# 5_Keyboard.net
KiCad netlist of a schematic drawn in Altium Designer
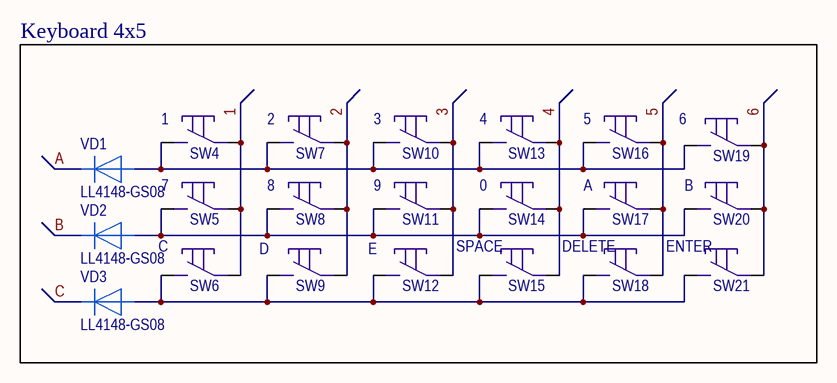
[diagram p0: 5_Keyboard.SchDoc]

(export (version "E")
  (design (tool "Eeschema 10.0.6"))
  (components
    (comp (ref "SW4")
      (value "KLS7-TS6604")
      (footprint "KLS7-TS6604-5.0-180-B")
      (libsource (lib "9.Commutation") (part "KLS7-TS6604"))
    )
    (comp (ref "SW5")
      (value "KLS7-TS6604")
      (footprint "KLS7-TS6604-5.0-180-B")
      (libsource (lib "9.Commutation") (part "KLS7-TS6604"))
    )
    (comp (ref "SW6")
      (value "KLS7-TS6604")
      (footprint "KLS7-TS6604-5.0-180-B")
      (libsource (lib "9.Commutation") (part "KLS7-TS6604"))
    )
    (comp (ref "SW7")
      (value "KLS7-TS6604")
      (footprint "KLS7-TS6604-5.0-180-B")
      (libsource (lib "9.Commutation") (part "KLS7-TS6604"))
    )
    (comp (ref "SW8")
      (value "KLS7-TS6604")
      (footprint "KLS7-TS6604-5.0-180-B")
      (libsource (lib "9.Commutation") (part "KLS7-TS6604"))
    )
    (comp (ref "SW9")
      (value "KLS7-TS6604")
      (footprint "KLS7-TS6604-5.0-180-B")
      (libsource (lib "9.Commutation") (part "KLS7-TS6604"))
    )
    (comp (ref "SW10")
      (value "KLS7-TS6604")
      (footprint "KLS7-TS6604-5.0-180-B")
      (libsource (lib "9.Commutation") (part "KLS7-TS6604"))
    )
    (comp (ref "SW11")
      (value "KLS7-TS6604")
      (footprint "KLS7-TS6604-5.0-180-B")
      (libsource (lib "9.Commutation") (part "KLS7-TS6604"))
    )
    (comp (ref "SW12")
      (value "KLS7-TS6604")
      (footprint "KLS7-TS6604-5.0-180-B")
      (libsource (lib "9.Commutation") (part "KLS7-TS6604"))
    )
    (comp (ref "SW13")
      (value "KLS7-TS6604")
      (footprint "KLS7-TS6604-5.0-180-B")
      (libsource (lib "9.Commutation") (part "KLS7-TS6604"))
    )
    (comp (ref "SW14")
      (value "KLS7-TS6604")
      (footprint "KLS7-TS6604-5.0-180-B")
      (libsource (lib "9.Commutation") (part "KLS7-TS6604"))
    )
    (comp (ref "SW15")
      (value "KLS7-TS6604")
      (footprint "KLS7-TS6604-5.0-180-B")
      (libsource (lib "9.Commutation") (part "KLS7-TS6604"))
    )
    (comp (ref "SW16")
      (value "KLS7-TS6604")
      (footprint "KLS7-TS6604-5.0-180-B")
      (libsource (lib "9.Commutation") (part "KLS7-TS6604"))
    )
    (comp (ref "SW17")
      (value "KLS7-TS6604")
      (footprint "KLS7-TS6604-5.0-180-B")
      (libsource (lib "9.Commutation") (part "KLS7-TS6604"))
    )
    (comp (ref "SW18")
      (value "KLS7-TS6604")
      (footprint "KLS7-TS6604-5.0-180-B")
      (libsource (lib "9.Commutation") (part "KLS7-TS6604"))
    )
    (comp (ref "SW19")
      (value "KLS7-TS6604")
      (footprint "KLS7-TS6604-5.0-180-B")
      (libsource (lib "9.Commutation") (part "KLS7-TS6604"))
    )
    (comp (ref "SW20")
      (value "KLS7-TS6604")
      (footprint "KLS7-TS6604-5.0-180-B")
      (libsource (lib "9.Commutation") (part "KLS7-TS6604"))
    )
    (comp (ref "SW21")
      (value "KLS7-TS6604")
      (footprint "KLS7-TS6604-5.0-180-B")
      (libsource (lib "9.Commutation") (part "KLS7-TS6604"))
    )
    (comp (ref "VD1")
      (value "LL4148-GS08")
      (footprint "SOD-80")
      (description "Диод")
      (libsource (lib "4.Diodes") (part "LL4148-GS08"))
    )
    (comp (ref "VD2")
      (value "LL4148-GS08")
      (footprint "SOD-80")
      (description "Диод")
      (libsource (lib "4.Diodes") (part "LL4148-GS08"))
    )
    (comp (ref "VD3")
      (value "LL4148-GS08")
      (footprint "SOD-80")
      (description "Диод")
      (libsource (lib "4.Diodes") (part "LL4148-GS08"))
    )
  )
  (nets
    (net (code "1") (name "/1") (class "Default")
      (node (ref "SW4") (pin "2") (pinfunction "2_2") (pintype "passive"))
      (node (ref "SW5") (pin "2") (pinfunction "2_2") (pintype "passive"))
      (node (ref "SW6") (pin "2") (pinfunction "2_2") (pintype "passive"))
    )
    (net (code "2") (name "/2") (class "Default")
      (node (ref "SW7") (pin "2") (pinfunction "2_2") (pintype "passive"))
      (node (ref "SW8") (pin "2") (pinfunction "2_2") (pintype "passive"))
      (node (ref "SW9") (pin "2") (pinfunction "2_2") (pintype "passive"))
    )
    (net (code "3") (name "/3") (class "Default")
      (node (ref "SW10") (pin "2") (pinfunction "2_2") (pintype "passive"))
      (node (ref "SW11") (pin "2") (pinfunction "2_2") (pintype "passive"))
      (node (ref "SW12") (pin "2") (pinfunction "2_2") (pintype "passive"))
    )
    (net (code "4") (name "/4") (class "Default")
      (node (ref "SW13") (pin "2") (pinfunction "2_2") (pintype "passive"))
      (node (ref "SW14") (pin "2") (pinfunction "2_2") (pintype "passive"))
      (node (ref "SW15") (pin "2") (pinfunction "2_2") (pintype "passive"))
    )
    (net (code "5") (name "/5") (class "Default")
      (node (ref "SW16") (pin "2") (pinfunction "2_2") (pintype "passive"))
      (node (ref "SW17") (pin "2") (pinfunction "2_2") (pintype "passive"))
      (node (ref "SW18") (pin "2") (pinfunction "2_2") (pintype "passive"))
    )
    (net (code "6") (name "/6") (class "Default")
      (node (ref "SW19") (pin "2") (pinfunction "2_2") (pintype "passive"))
      (node (ref "SW20") (pin "2") (pinfunction "2_2") (pintype "passive"))
      (node (ref "SW21") (pin "2") (pinfunction "2_2") (pintype "passive"))
    )
    (net (code "7") (name "/A") (class "Default")
      (node (ref "VD1") (pin "2") (pinfunction "2_2") (pintype "passive"))
    )
    (net (code "8") (name "/B") (class "Default")
      (node (ref "VD2") (pin "2") (pinfunction "2_2") (pintype "passive"))
    )
    (net (code "9") (name "/C") (class "Default")
      (node (ref "VD3") (pin "2") (pinfunction "2_2") (pintype "passive"))
    )
    (net (code "10") (name "Net-(SW10-Pad1)") (class "Default")
      (node (ref "SW10") (pin "1") (pinfunction "1_1") (pintype "passive"))
      (node (ref "SW13") (pin "1") (pinfunction "1_1") (pintype "passive"))
      (node (ref "SW16") (pin "1") (pinfunction "1_1") (pintype "passive"))
      (node (ref "SW19") (pin "1") (pinfunction "1_1") (pintype "passive"))
      (node (ref "SW4") (pin "1") (pinfunction "1_1") (pintype "passive"))
      (node (ref "SW7") (pin "1") (pinfunction "1_1") (pintype "passive"))
      (node (ref "VD1") (pin "1") (pinfunction "1_1") (pintype "passive"))
    )
    (net (code "11") (name "Net-(SW11-Pad1)") (class "Default")
      (node (ref "SW11") (pin "1") (pinfunction "1_1") (pintype "passive"))
      (node (ref "SW14") (pin "1") (pinfunction "1_1") (pintype "passive"))
      (node (ref "SW17") (pin "1") (pinfunction "1_1") (pintype "passive"))
      (node (ref "SW20") (pin "1") (pinfunction "1_1") (pintype "passive"))
      (node (ref "SW5") (pin "1") (pinfunction "1_1") (pintype "passive"))
      (node (ref "SW8") (pin "1") (pinfunction "1_1") (pintype "passive"))
      (node (ref "VD2") (pin "1") (pinfunction "1_1") (pintype "passive"))
    )
    (net (code "12") (name "Net-(SW12-Pad1)") (class "Default")
      (node (ref "SW12") (pin "1") (pinfunction "1_1") (pintype "passive"))
      (node (ref "SW15") (pin "1") (pinfunction "1_1") (pintype "passive"))
      (node (ref "SW18") (pin "1") (pinfunction "1_1") (pintype "passive"))
      (node (ref "SW21") (pin "1") (pinfunction "1_1") (pintype "passive"))
      (node (ref "SW6") (pin "1") (pinfunction "1_1") (pintype "passive"))
      (node (ref "SW9") (pin "1") (pinfunction "1_1") (pintype "passive"))
      (node (ref "VD3") (pin "1") (pinfunction "1_1") (pintype "passive"))
    )
  )
)
